# USB_SUPPLY.net
KiCad netlist of a schematic drawn in EAGLE
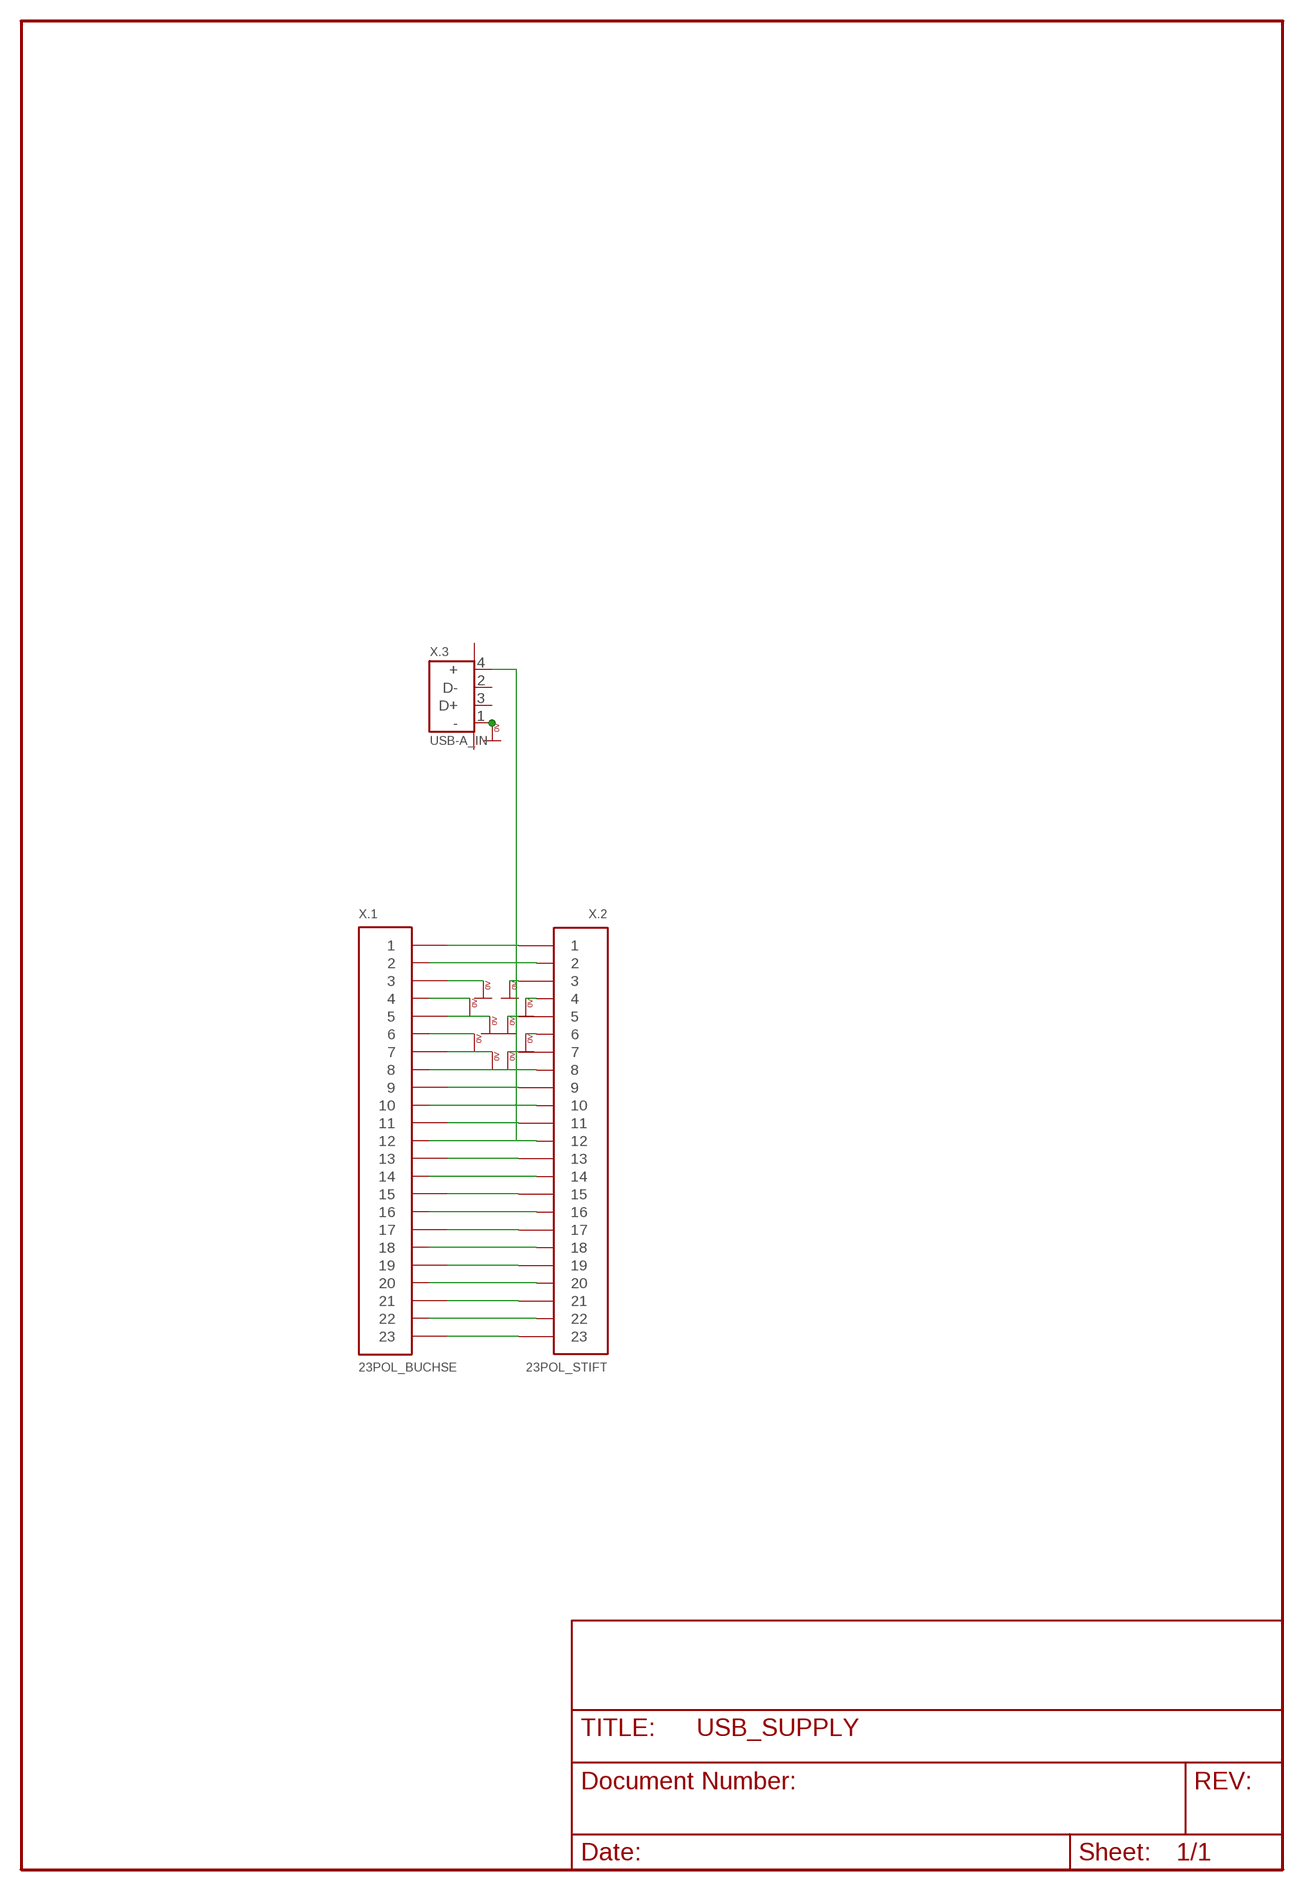
[diagram p0: schematic, sheet 1]

(export (version "E")
  (design (tool "Eeschema 10.0.6"))
  (components
    (comp (ref "X.1")
      (value "23POL_BUCHSE")
      (footprint "eagle-import:SUB-D_23F_L")
      (libsource (lib "eagle-import") (part "23POL_BUCHSE"))
    )
    (comp (ref "X.2")
      (value "23POL_STIFT")
      (footprint "eagle-import:SUB-D_23M_L")
      (libsource (lib "eagle-import") (part "23POL_STIFT"))
    )
    (comp (ref "X.3")
      (value "USB-A_IN")
      (footprint "eagle-import:USB-A-90_IN")
      (libsource (lib "eagle-import") (part "USB-A_IN"))
    )
  )
  (nets
    (net (code "1") (name "0V") (class "Default")
      (node (ref "X.1") (pin "3") (pinfunction "3_3") (pintype "passive"))
      (node (ref "X.1") (pin "4") (pinfunction "4_4") (pintype "passive"))
      (node (ref "X.1") (pin "5") (pinfunction "5_5") (pintype "passive"))
      (node (ref "X.1") (pin "6") (pinfunction "6_6") (pintype "passive"))
      (node (ref "X.1") (pin "7") (pinfunction "7_7") (pintype "passive"))
      (node (ref "X.2") (pin "3") (pinfunction "3_3") (pintype "passive"))
      (node (ref "X.2") (pin "4") (pinfunction "4_4") (pintype "passive"))
      (node (ref "X.2") (pin "5") (pinfunction "5_5") (pintype "passive"))
      (node (ref "X.2") (pin "6") (pinfunction "6_6") (pintype "passive"))
      (node (ref "X.2") (pin "7") (pinfunction "7_7") (pintype "passive"))
      (node (ref "X.3") (pin "1") (pinfunction "-_1") (pintype "bidirectional"))
    )
    (net (code "2") (name "Net-(X.1-Pad1)") (class "Default")
      (node (ref "X.1") (pin "1") (pinfunction "1_1") (pintype "passive"))
      (node (ref "X.2") (pin "1") (pinfunction "1_1") (pintype "passive"))
    )
    (net (code "3") (name "Net-(X.1-Pad2)") (class "Default")
      (node (ref "X.1") (pin "2") (pinfunction "2_2") (pintype "passive"))
      (node (ref "X.2") (pin "2") (pinfunction "2_2") (pintype "passive"))
    )
    (net (code "4") (name "Net-(X.1-Pad8)") (class "Default")
      (node (ref "X.1") (pin "8") (pinfunction "8_8") (pintype "passive"))
      (node (ref "X.2") (pin "8") (pinfunction "8_8") (pintype "passive"))
    )
    (net (code "5") (name "Net-(X.1-Pad9)") (class "Default")
      (node (ref "X.1") (pin "9") (pinfunction "9_9") (pintype "passive"))
      (node (ref "X.2") (pin "9") (pinfunction "9_9") (pintype "passive"))
    )
    (net (code "6") (name "Net-(X.1-Pad10)") (class "Default")
      (node (ref "X.1") (pin "10") (pinfunction "10_10") (pintype "passive"))
      (node (ref "X.2") (pin "10") (pinfunction "10_10") (pintype "passive"))
    )
    (net (code "7") (name "Net-(X.1-Pad11)") (class "Default")
      (node (ref "X.1") (pin "11") (pinfunction "11_11") (pintype "passive"))
      (node (ref "X.2") (pin "11") (pinfunction "11_11") (pintype "passive"))
    )
    (net (code "8") (name "Net-(X.1-Pad13)") (class "Default")
      (node (ref "X.1") (pin "13") (pinfunction "13_13") (pintype "passive"))
      (node (ref "X.2") (pin "13") (pinfunction "13_13") (pintype "passive"))
    )
    (net (code "9") (name "Net-(X.1-Pad14)") (class "Default")
      (node (ref "X.1") (pin "14") (pinfunction "14_14") (pintype "passive"))
      (node (ref "X.2") (pin "14") (pinfunction "14_14") (pintype "passive"))
    )
    (net (code "10") (name "Net-(X.1-Pad15)") (class "Default")
      (node (ref "X.1") (pin "15") (pinfunction "15_15") (pintype "passive"))
      (node (ref "X.2") (pin "15") (pinfunction "15_15") (pintype "passive"))
    )
    (net (code "11") (name "Net-(X.1-Pad16)") (class "Default")
      (node (ref "X.1") (pin "16") (pinfunction "16_16") (pintype "passive"))
      (node (ref "X.2") (pin "16") (pinfunction "16_16") (pintype "passive"))
    )
    (net (code "12") (name "Net-(X.1-Pad17)") (class "Default")
      (node (ref "X.1") (pin "17") (pinfunction "17_17") (pintype "passive"))
      (node (ref "X.2") (pin "17") (pinfunction "17_17") (pintype "passive"))
    )
    (net (code "13") (name "Net-(X.1-Pad18)") (class "Default")
      (node (ref "X.1") (pin "18") (pinfunction "18_18") (pintype "passive"))
      (node (ref "X.2") (pin "18") (pinfunction "18_18") (pintype "passive"))
    )
    (net (code "14") (name "Net-(X.1-Pad19)") (class "Default")
      (node (ref "X.1") (pin "19") (pinfunction "19_19") (pintype "passive"))
      (node (ref "X.2") (pin "19") (pinfunction "19_19") (pintype "passive"))
    )
    (net (code "15") (name "Net-(X.1-Pad20)") (class "Default")
      (node (ref "X.1") (pin "20") (pinfunction "20_20") (pintype "passive"))
      (node (ref "X.2") (pin "20") (pinfunction "20_20") (pintype "passive"))
    )
    (net (code "16") (name "Net-(X.1-Pad21)") (class "Default")
      (node (ref "X.1") (pin "21") (pinfunction "21_21") (pintype "passive"))
      (node (ref "X.2") (pin "21") (pinfunction "21_21") (pintype "passive"))
    )
    (net (code "17") (name "Net-(X.1-Pad22)") (class "Default")
      (node (ref "X.1") (pin "22") (pinfunction "22_22") (pintype "passive"))
      (node (ref "X.2") (pin "22") (pinfunction "22_22") (pintype "passive"))
    )
    (net (code "18") (name "Net-(X.1-Pad23)") (class "Default")
      (node (ref "X.1") (pin "23") (pinfunction "23_23") (pintype "passive"))
      (node (ref "X.2") (pin "23") (pinfunction "23_23") (pintype "passive"))
    )
    (net (code "19") (name "Net-(X.3-+)") (class "Default")
      (node (ref "X.1") (pin "12") (pinfunction "12_12") (pintype "passive"))
      (node (ref "X.2") (pin "12") (pinfunction "12_12") (pintype "passive"))
      (node (ref "X.3") (pin "4") (pinfunction "+_4") (pintype "bidirectional"))
    )
    (net (code "20") (name "unconnected-(X.3-D+-Pad3)") (class "Default")
      (node (ref "X.3") (pin "3") (pinfunction "D+_3") (pintype "bidirectional"))
    )
    (net (code "21") (name "unconnected-(X.3-D--Pad2)") (class "Default")
      (node (ref "X.3") (pin "2") (pinfunction "D-_2") (pintype "bidirectional"))
    )
    (net (code "22") (name "unconnected-(X.3-GND-PadP$1)") (class "Default")
      (node (ref "X.3") (pin "P$1") (pinfunction "GND_P$1") (pintype "bidirectional"))
    )
    (net (code "23") (name "unconnected-(X.3-GND-PadP$2)") (class "Default")
      (node (ref "X.3") (pin "P$2") (pinfunction "GND_P$2") (pintype "bidirectional"))
    )
  )
)
